# STM32F407_3.net
KiCad netlist of a schematic drawn in Altium Designer
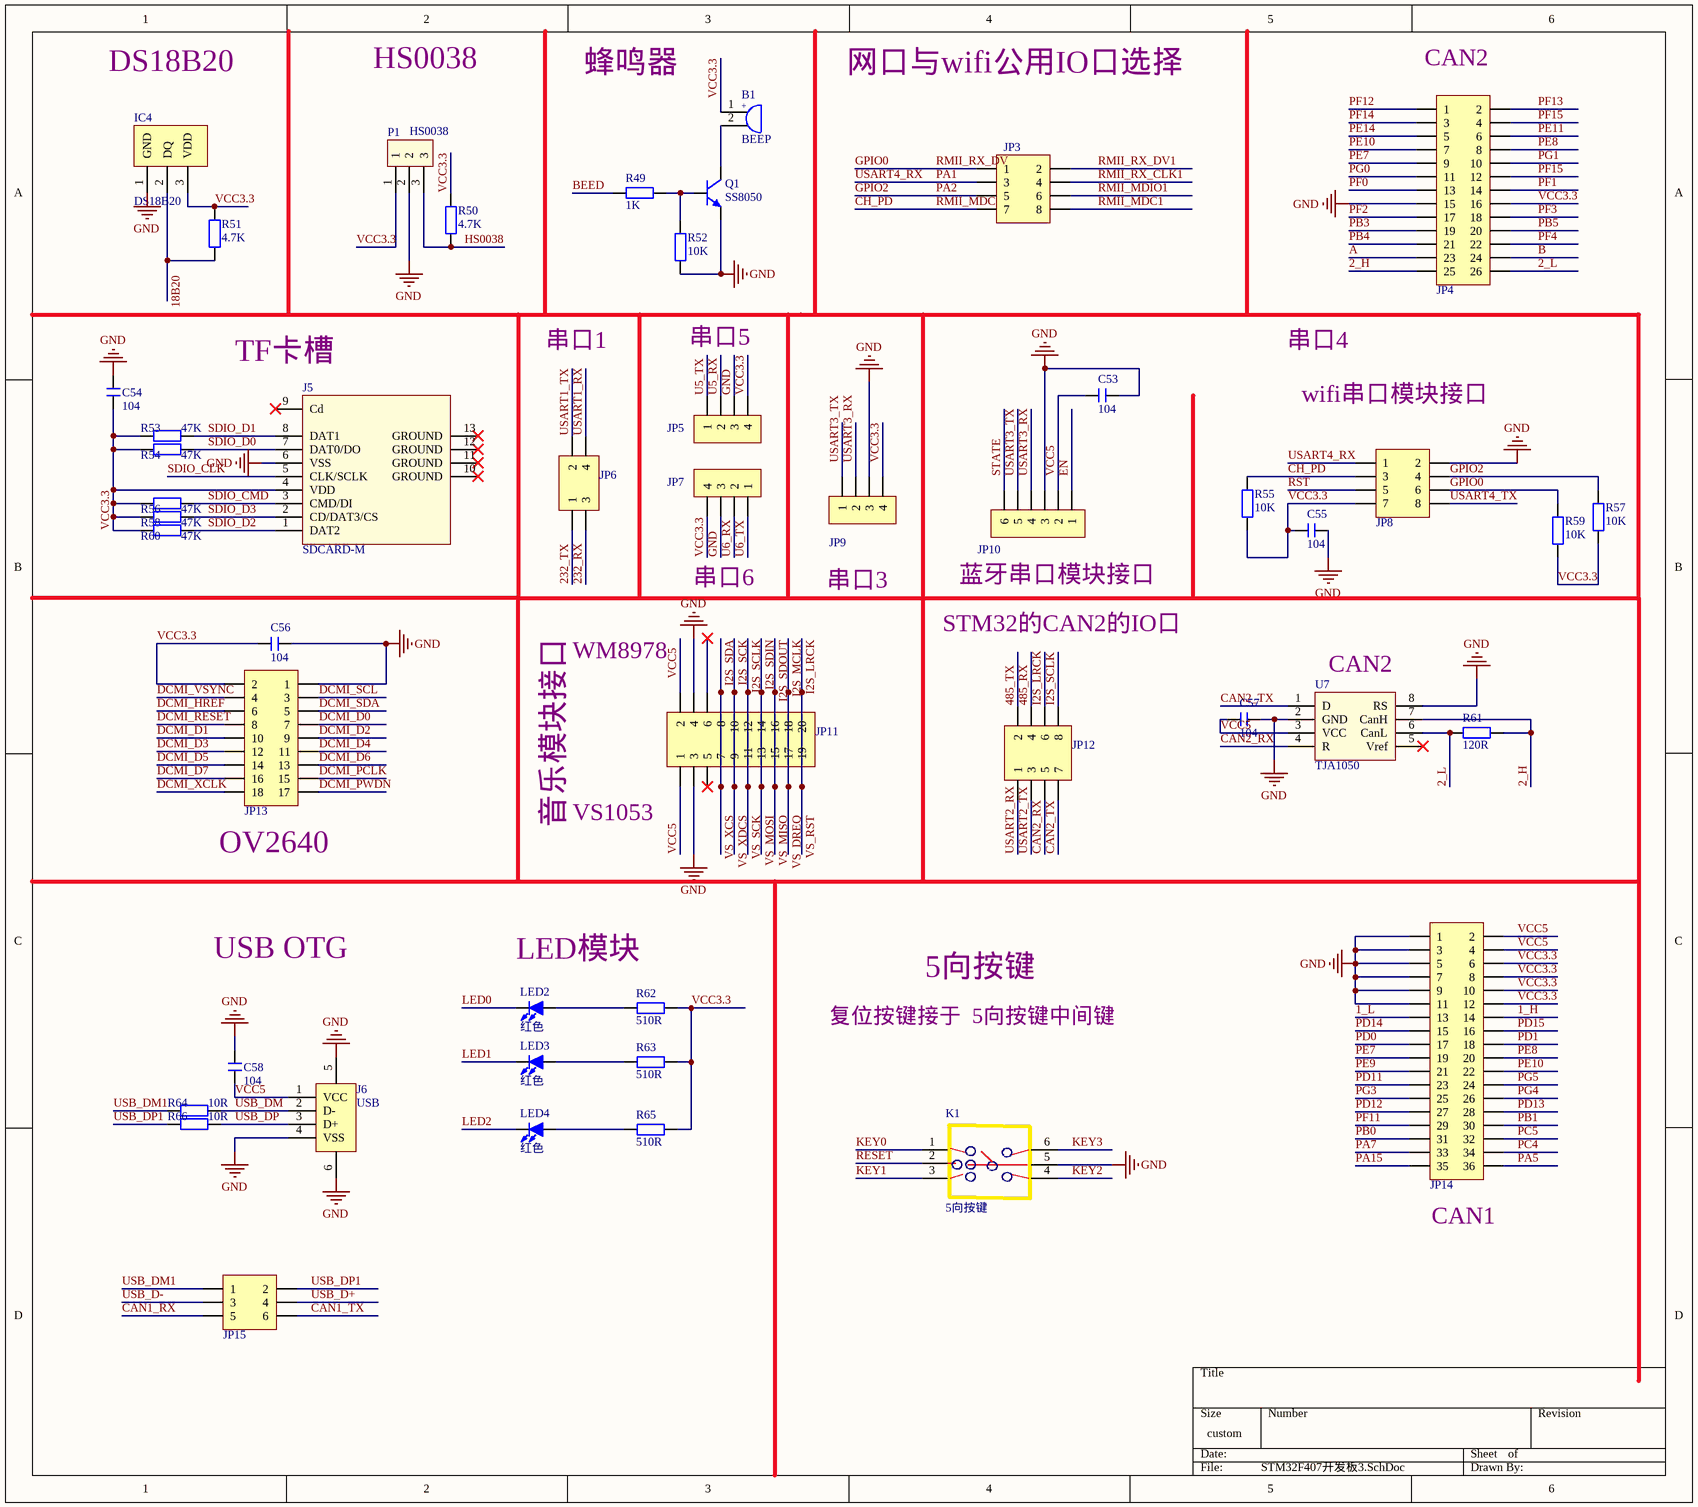
[diagram p0: STM32F407开发板3.SchDoc]

(export (version "E")
  (design (tool "Eeschema 10.0.6"))
  (components
    (comp (ref "B1")
      (value "BEEP")
      (footprint "BEEP 5x9x5.5")
      (description "蜂鸣器")
      (fields (field (name "版权归属") "源创客"))
      (libsource (lib "未分类器件") (part "BEEP"))
    )
    (comp (ref "C53")
      (value "104")
      (footprint "C 0603")
      (description "无极性贴片电容")
      (fields (field (name "版权归属") "源创客"))
      (libsource (lib "电阻-电容-电感") (part "C"))
    )
    (comp (ref "C54")
      (value "104")
      (footprint "C 0603")
      (description "无极性贴片电容")
      (fields (field (name "版权归属") "源创客"))
      (libsource (lib "电阻-电容-电感") (part "C"))
    )
    (comp (ref "C55")
      (value "104")
      (footprint "C 0603")
      (description "无极性贴片电容")
      (fields (field (name "版权归属") "源创客"))
      (libsource (lib "电阻-电容-电感") (part "C"))
    )
    (comp (ref "C56")
      (value "104")
      (footprint "C 0603")
      (description "无极性贴片电容")
      (fields (field (name "版权归属") "源创客"))
      (libsource (lib "电阻-电容-电感") (part "C"))
    )
    (comp (ref "C57")
      (value "104")
      (footprint "C 0603")
      (description "无极性贴片电容")
      (fields (field (name "版权归属") "源创客"))
      (libsource (lib "电阻-电容-电感") (part "C"))
    )
    (comp (ref "C58")
      (value "104")
      (footprint "C 0603")
      (description "无极性贴片电容")
      (fields (field (name "版权归属") "源创客"))
      (libsource (lib "电阻-电容-电感") (part "C"))
    )
    (comp (ref "IC4")
      (value "DS18B20")
      (footprint "TO92A")
      (description "数字温度计")
      (fields (field (name "版权归属") "源创客"))
      (libsource (lib "IC芯片") (part "DS18B20"))
    )
    (comp (ref "J5")
      (value "SDCARD-M")
      (footprint "Micro TF/SD")
      (description "TF卡槽")
      (libsource (lib "接口类") (part "SDCARD-M"))
    )
    (comp (ref "J6") (value "USB") (footprint "USB-A/S_A") (libsource (lib "接口类") (part "USB OTG")))
    (comp (ref "JP3")
      (value "Header 4X2")
      (footprint "HDR-4X2")
      (description "4*2P接插件")
      (fields (field (name "版权归属") "源创客"))
      (libsource (lib "") (part "Header 4X2_1"))
    )
    (comp (ref "JP4")
      (value "Header 2X11")
      (footprint "HDR-13X2")
      (description "13*2P接插件")
      (fields (field (name "版权归属") "源创客"))
      (libsource (lib "接插件") (part "Header 13X2"))
    )
    (comp (ref "JP5")
      (value "HDR-1X4")
      (footprint "HDR-1X4")
      (description "4P接插件")
      (fields (field (name "版权归属") "源创客"))
      (libsource (lib "接插件") (part "Header 4"))
    )
    (comp (ref "JP6")
      (value "Header2X2")
      (footprint "HDR-2X2")
      (description "2*2P接插件")
      (fields (field (name "版权归属") "源创客"))
      (libsource (lib "接插件") (part "Header 2X2"))
    )
    (comp (ref "JP7")
      (value "HDR-1X4")
      (footprint "HDR-1X4")
      (description "4P接插件")
      (fields (field (name "版权归属") "源创客"))
      (libsource (lib "") (part "Header 4_1"))
    )
    (comp (ref "JP8")
      (value "Header 4X2")
      (footprint "HDR-4X2")
      (description "4*2P接插件")
      (fields (field (name "版权归属") "源创客"))
      (libsource (lib "") (part "Header 4X2_1"))
    )
    (comp (ref "JP9")
      (value "HDR-1X4")
      (footprint "HDR-1X4")
      (description "4P接插件")
      (fields (field (name "版权归属") "源创客"))
      (libsource (lib "接插件") (part "Header 4"))
    )
    (comp (ref "JP10")
      (value "HDR-1X6")
      (footprint "HDR-1X6")
      (description "6P接插件")
      (fields (field (name "版权归属") "源创客"))
      (libsource (lib "接插件") (part "Header 6"))
    )
    (comp (ref "JP11")
      (value "Header 2X10")
      (footprint "HDR-10X2")
      (description "10*2P接插件")
      (fields (field (name "版权归属") "源创客"))
      (libsource (lib "接插件") (part "Header 10X2"))
    )
    (comp (ref "JP12")
      (value "Header 4X2")
      (footprint "HDR-4X2")
      (description "4*2P接插件")
      (fields (field (name "版权归属") "源创客"))
      (libsource (lib "接插件") (part "Header 4X2"))
    )
    (comp (ref "JP13")
      (value "Header 9X2")
      (footprint "HDR-9X2")
      (description "9*2P接插件")
      (fields (field (name "版权归属") "源创客"))
      (libsource (lib "接插件") (part "Header 9X2"))
    )
    (comp (ref "JP14")
      (value "Header 2X11")
      (footprint "HDR-18X2")
      (description "18*2P接插件")
      (fields (field (name "版权归属") "源创客"))
      (libsource (lib "接插件") (part "Header 18X2"))
    )
    (comp (ref "JP15")
      (value "Header3X2")
      (footprint "HDR-3X2")
      (description "3*2P接插件")
      (fields (field (name "版权归属") "源创客"))
      (libsource (lib "接插件") (part "Header 3X2"))
    )
    (comp (ref "K1") (value "5向按键") (footprint "五向按键") (libsource (lib "按键-开关") (part "5向按键")))
    (comp (ref "LED2")
      (value "红色")
      (footprint "LED 0603R")
      (description "5mm插件LED")
      (fields (field (name "版权归属") "源创客"))
      (libsource (lib "LED") (part "LED-5MM"))
    )
    (comp (ref "LED3")
      (value "红色")
      (footprint "LED 0603R")
      (description "5mm插件LED")
      (fields (field (name "版权归属") "源创客"))
      (libsource (lib "LED") (part "LED-5MM"))
    )
    (comp (ref "LED4")
      (value "红色")
      (footprint "LED 0603R")
      (description "5mm插件LED")
      (fields (field (name "版权归属") "源创客"))
      (libsource (lib "LED") (part "LED-5MM"))
    )
    (comp (ref "P1") (value "HS0038") (footprint "VS1838B-A") (libsource (lib "传感元件") (part "HS0038")))
    (comp (ref "Q1")
      (value "SS8050")
      (footprint "SOT23-3L")
      (description "高频放大-NPN型")
      (fields (field (name "版权归属") "源创客"))
      (libsource (lib "三极管") (part "8050-SMD"))
    )
    (comp (ref "R49")
      (value "1K")
      (footprint "R 0603")
      (description "贴片电阻")
      (fields (field (name "版权归属") "源创客"))
      (libsource (lib "电阻-电容-电感") (part "R"))
    )
    (comp (ref "R50")
      (value "4.7K")
      (footprint "R 0603")
      (description "贴片电阻")
      (fields (field (name "版权归属") "源创客"))
      (libsource (lib "电阻-电容-电感") (part "R"))
    )
    (comp (ref "R51")
      (value "4.7K")
      (footprint "R 0603")
      (description "贴片电阻")
      (fields (field (name "版权归属") "源创客"))
      (libsource (lib "电阻-电容-电感") (part "R"))
    )
    (comp (ref "R52")
      (value "10K")
      (footprint "R 0603")
      (description "贴片电阻")
      (fields (field (name "版权归属") "源创客"))
      (libsource (lib "电阻-电容-电感") (part "R"))
    )
    (comp (ref "R53")
      (value "47K")
      (footprint "R 0603")
      (description "贴片电阻")
      (fields (field (name "版权归属") "源创客"))
      (libsource (lib "电阻-电容-电感") (part "R"))
    )
    (comp (ref "R54")
      (value "47K")
      (footprint "R 0603")
      (description "贴片电阻")
      (fields (field (name "版权归属") "源创客"))
      (libsource (lib "电阻-电容-电感") (part "R"))
    )
    (comp (ref "R55")
      (value "10K")
      (footprint "R 0603")
      (description "贴片电阻")
      (fields (field (name "版权归属") "源创客"))
      (libsource (lib "电阻-电容-电感") (part "R"))
    )
    (comp (ref "R56")
      (value "47K")
      (footprint "R 0603")
      (description "贴片电阻")
      (fields (field (name "版权归属") "源创客"))
      (libsource (lib "电阻-电容-电感") (part "R"))
    )
    (comp (ref "R57")
      (value "10K")
      (footprint "R 0603")
      (description "贴片电阻")
      (fields (field (name "版权归属") "源创客"))
      (libsource (lib "电阻-电容-电感") (part "R"))
    )
    (comp (ref "R58")
      (value "47K")
      (footprint "R 0603")
      (description "贴片电阻")
      (fields (field (name "版权归属") "源创客"))
      (libsource (lib "电阻-电容-电感") (part "R"))
    )
    (comp (ref "R59")
      (value "10K")
      (footprint "R 0603")
      (description "贴片电阻")
      (fields (field (name "版权归属") "源创客"))
      (libsource (lib "电阻-电容-电感") (part "R"))
    )
    (comp (ref "R60")
      (value "47K")
      (footprint "R 0603")
      (description "贴片电阻")
      (fields (field (name "版权归属") "源创客"))
      (libsource (lib "电阻-电容-电感") (part "R"))
    )
    (comp (ref "R61")
      (value "120R")
      (footprint "R 0603")
      (description "贴片电阻")
      (fields (field (name "版权归属") "源创客"))
      (libsource (lib "电阻-电容-电感") (part "R"))
    )
    (comp (ref "R62")
      (value "510R")
      (footprint "R 0603")
      (description "贴片电阻")
      (fields (field (name "版权归属") "源创客"))
      (libsource (lib "电阻-电容-电感") (part "R"))
    )
    (comp (ref "R63")
      (value "510R")
      (footprint "R 0603")
      (description "贴片电阻")
      (fields (field (name "版权归属") "源创客"))
      (libsource (lib "电阻-电容-电感") (part "R"))
    )
    (comp (ref "R64")
      (value "10R")
      (footprint "R 0603")
      (description "贴片电阻")
      (fields (field (name "版权归属") "源创客"))
      (libsource (lib "电阻-电容-电感") (part "R"))
    )
    (comp (ref "R65")
      (value "510R")
      (footprint "R 0603")
      (description "贴片电阻")
      (fields (field (name "版权归属") "源创客"))
      (libsource (lib "电阻-电容-电感") (part "R"))
    )
    (comp (ref "R66")
      (value "10R")
      (footprint "R 0603")
      (description "贴片电阻")
      (fields (field (name "版权归属") "源创客"))
      (libsource (lib "电阻-电容-电感") (part "R"))
    )
    (comp (ref "U7") (value "TJA1050") (footprint "TJA1050") (libsource (lib "IC芯片") (part "TJA1050")))
  )
  (nets
    (net (code "1") (name "/1_H") (class "Default")
      (node (ref "JP14") (pin "14") (pinfunction "14_14") (pintype "passive"))
    )
    (net (code "2") (name "/1_L") (class "Default")
      (node (ref "JP14") (pin "13") (pinfunction "13_13") (pintype "passive"))
    )
    (net (code "3") (name "/2_H") (class "Default")
      (node (ref "JP4") (pin "25") (pinfunction "25_25") (pintype "passive"))
      (node (ref "R61") (pin "1") (pinfunction "1_1") (pintype "passive"))
      (node (ref "U7") (pin "7") (pinfunction "CanH_7") (pintype "passive"))
    )
    (net (code "4") (name "/2_L") (class "Default")
      (node (ref "JP4") (pin "26") (pinfunction "26_26") (pintype "passive"))
      (node (ref "R61") (pin "2") (pinfunction "2_2") (pintype "passive"))
      (node (ref "U7") (pin "6") (pinfunction "CanL_6") (pintype "passive"))
    )
    (net (code "5") (name "/18B20") (class "Default")
      (node (ref "IC4") (pin "2") (pinfunction "DQ_2") (pintype "passive"))
      (node (ref "R51") (pin "1") (pinfunction "1_1") (pintype "passive"))
    )
    (net (code "6") (name "/232_RX") (class "Default")
      (node (ref "JP6") (pin "3") (pinfunction "3_3") (pintype "passive"))
    )
    (net (code "7") (name "/232_TX") (class "Default")
      (node (ref "JP6") (pin "1") (pinfunction "1_1") (pintype "passive"))
    )
    (net (code "8") (name "/485_RX") (class "Default")
      (node (ref "JP12") (pin "4") (pinfunction "4_4") (pintype "passive"))
    )
    (net (code "9") (name "/485_TX") (class "Default")
      (node (ref "JP12") (pin "2") (pinfunction "2_2") (pintype "passive"))
    )
    (net (code "10") (name "/A") (class "Default")
      (node (ref "JP4") (pin "23") (pinfunction "23_23") (pintype "passive"))
    )
    (net (code "11") (name "/B") (class "Default")
      (node (ref "JP4") (pin "24") (pinfunction "24_24") (pintype "passive"))
    )
    (net (code "12") (name "/BEED") (class "Default")
      (node (ref "R49") (pin "2") (pinfunction "2_2") (pintype "passive"))
    )
    (net (code "13") (name "/CAN1_RX") (class "Default")
      (node (ref "JP15") (pin "5") (pinfunction "5_5") (pintype "passive"))
    )
    (net (code "14") (name "/CAN1_TX") (class "Default")
      (node (ref "JP15") (pin "6") (pinfunction "6_6") (pintype "passive"))
    )
    (net (code "15") (name "/CAN2_RX") (class "Default")
      (node (ref "JP12") (pin "5") (pinfunction "5_5") (pintype "passive"))
      (node (ref "U7") (pin "4") (pinfunction "R_4") (pintype "passive"))
    )
    (net (code "16") (name "/CAN2_TX") (class "Default")
      (node (ref "JP12") (pin "7") (pinfunction "7_7") (pintype "passive"))
      (node (ref "U7") (pin "1") (pinfunction "D_1") (pintype "passive"))
    )
    (net (code "17") (name "/CH_PD") (class "Default")
      (node (ref "JP3") (pin "7") (pinfunction "7_7") (pintype "passive"))
      (node (ref "JP8") (pin "3") (pinfunction "3_3") (pintype "passive"))
      (node (ref "R55") (pin "2") (pinfunction "2_2") (pintype "passive"))
    )
    (net (code "18") (name "/DCMI_D0") (class "Default")
      (node (ref "JP13") (pin "7") (pinfunction "7_7") (pintype "passive"))
    )
    (net (code "19") (name "/DCMI_D1") (class "Default")
      (node (ref "JP13") (pin "10") (pinfunction "10_10") (pintype "passive"))
    )
    (net (code "20") (name "/DCMI_D2") (class "Default")
      (node (ref "JP13") (pin "9") (pinfunction "9_9") (pintype "passive"))
    )
    (net (code "21") (name "/DCMI_D3") (class "Default")
      (node (ref "JP13") (pin "12") (pinfunction "12_12") (pintype "passive"))
    )
    (net (code "22") (name "/DCMI_D4") (class "Default")
      (node (ref "JP13") (pin "11") (pinfunction "11_11") (pintype "passive"))
    )
    (net (code "23") (name "/DCMI_D5") (class "Default")
      (node (ref "JP13") (pin "14") (pinfunction "14_14") (pintype "passive"))
    )
    (net (code "24") (name "/DCMI_D6") (class "Default")
      (node (ref "JP13") (pin "13") (pinfunction "13_13") (pintype "passive"))
    )
    (net (code "25") (name "/DCMI_D7") (class "Default")
      (node (ref "JP13") (pin "16") (pinfunction "16_16") (pintype "passive"))
    )
    (net (code "26") (name "/DCMI_HREF") (class "Default")
      (node (ref "JP13") (pin "6") (pinfunction "6_6") (pintype "passive"))
    )
    (net (code "27") (name "/DCMI_PCLK") (class "Default")
      (node (ref "JP13") (pin "15") (pinfunction "15_15") (pintype "passive"))
    )
    (net (code "28") (name "/DCMI_PWDN") (class "Default")
      (node (ref "JP13") (pin "17") (pinfunction "17_17") (pintype "passive"))
    )
    (net (code "29") (name "/DCMI_RESET") (class "Default")
      (node (ref "JP13") (pin "8") (pinfunction "8_8") (pintype "passive"))
    )
    (net (code "30") (name "/DCMI_SCL") (class "Default")
      (node (ref "JP13") (pin "3") (pinfunction "3_3") (pintype "passive"))
    )
    (net (code "31") (name "/DCMI_SDA") (class "Default")
      (node (ref "JP13") (pin "5") (pinfunction "5_5") (pintype "passive"))
    )
    (net (code "32") (name "/DCMI_VSYNC") (class "Default")
      (node (ref "JP13") (pin "4") (pinfunction "4_4") (pintype "passive"))
    )
    (net (code "33") (name "/DCMI_XCLK") (class "Default")
      (node (ref "JP13") (pin "18") (pinfunction "18_18") (pintype "passive"))
    )
    (net (code "34") (name "/EN") (class "Default")
      (node (ref "JP10") (pin "1") (pinfunction "1_1") (pintype "passive"))
    )
    (net (code "35") (name "/GPIO0") (class "Default")
      (node (ref "JP3") (pin "1") (pinfunction "1_1") (pintype "passive"))
      (node (ref "JP8") (pin "6") (pinfunction "6_6") (pintype "passive"))
      (node (ref "R59") (pin "2") (pinfunction "2_2") (pintype "passive"))
    )
    (net (code "36") (name "/GPIO2") (class "Default")
      (node (ref "JP3") (pin "5") (pinfunction "5_5") (pintype "passive"))
      (node (ref "JP8") (pin "4") (pinfunction "4_4") (pintype "passive"))
      (node (ref "R57") (pin "2") (pinfunction "2_2") (pintype "passive"))
    )
    (net (code "37") (name "/HS0038") (class "Default")
      (node (ref "P1") (pin "3") (pinfunction "3_3") (pintype "passive"))
      (node (ref "R50") (pin "1") (pinfunction "1_1") (pintype "passive"))
    )
    (net (code "38") (name "/I2S_LRCK") (class "Default")
      (node (ref "JP11") (pin "19") (pinfunction "19_19") (pintype "passive"))
      (node (ref "JP11") (pin "20") (pinfunction "20_20") (pintype "passive"))
      (node (ref "JP12") (pin "6") (pinfunction "6_6") (pintype "passive"))
    )
    (net (code "39") (name "/I2S_MCLK") (class "Default")
      (node (ref "JP11") (pin "17") (pinfunction "17_17") (pintype "passive"))
      (node (ref "JP11") (pin "18") (pinfunction "18_18") (pintype "passive"))
    )
    (net (code "40") (name "/I2S_SCK") (class "Default")
      (node (ref "JP11") (pin "10") (pinfunction "10_10") (pintype "passive"))
      (node (ref "JP11") (pin "9") (pinfunction "9_9") (pintype "passive"))
    )
    (net (code "41") (name "/I2S_SCLK") (class "Default")
      (node (ref "JP11") (pin "11") (pinfunction "11_11") (pintype "passive"))
      (node (ref "JP11") (pin "12") (pinfunction "12_12") (pintype "passive"))
      (node (ref "JP12") (pin "8") (pinfunction "8_8") (pintype "passive"))
    )
    (net (code "42") (name "/I2S_SDA") (class "Default")
      (node (ref "JP11") (pin "7") (pinfunction "7_7") (pintype "passive"))
      (node (ref "JP11") (pin "8") (pinfunction "8_8") (pintype "passive"))
    )
    (net (code "43") (name "/I2S_SDIN") (class "Default")
      (node (ref "JP11") (pin "13") (pinfunction "13_13") (pintype "passive"))
      (node (ref "JP11") (pin "14") (pinfunction "14_14") (pintype "passive"))
    )
    (net (code "44") (name "/I2S_SDOUT") (class "Default")
      (node (ref "JP11") (pin "15") (pinfunction "15_15") (pintype "passive"))
      (node (ref "JP11") (pin "16") (pinfunction "16_16") (pintype "passive"))
    )
    (net (code "45") (name "/KEY0") (class "Default")
      (node (ref "K1") (pin "1") (pinfunction "1_1") (pintype "passive"))
    )
    (net (code "46") (name "/KEY1") (class "Default")
      (node (ref "K1") (pin "3") (pinfunction "3_3") (pintype "passive"))
    )
    (net (code "47") (name "/KEY2") (class "Default")
      (node (ref "K1") (pin "4") (pinfunction "4_4") (pintype "passive"))
    )
    (net (code "48") (name "/KEY3") (class "Default")
      (node (ref "K1") (pin "6") (pinfunction "6_6") (pintype "passive"))
    )
    (net (code "49") (name "/LED0") (class "Default")
      (node (ref "LED2") (pin "2") (pinfunction "K_2") (pintype "passive"))
    )
    (net (code "50") (name "/LED1") (class "Default")
      (node (ref "LED3") (pin "2") (pinfunction "K_2") (pintype "passive"))
    )
    (net (code "51") (name "/LED2") (class "Default")
      (node (ref "LED4") (pin "2") (pinfunction "K_2") (pintype "passive"))
    )
    (net (code "52") (name "/PA1") (class "Default")
      (node (ref "JP3") (pin "3") (pinfunction "3_3") (pintype "passive"))
      (node (ref "JP8") (pin "1") (pinfunction "1_1") (pintype "passive"))
    )
    (net (code "53") (name "/PA5") (class "Default")
      (node (ref "JP14") (pin "36") (pinfunction "36_36") (pintype "passive"))
    )
    (net (code "54") (name "/PA7") (class "Default")
      (node (ref "JP14") (pin "33") (pinfunction "33_33") (pintype "passive"))
    )
    (net (code "55") (name "/PA15") (class "Default")
      (node (ref "JP14") (pin "35") (pinfunction "35_35") (pintype "passive"))
    )
    (net (code "56") (name "/PB0") (class "Default")
      (node (ref "JP14") (pin "31") (pinfunction "31_31") (pintype "passive"))
    )
    (net (code "57") (name "/PB1") (class "Default")
      (node (ref "JP14") (pin "30") (pinfunction "30_30") (pintype "passive"))
    )
    (net (code "58") (name "/PB3") (class "Default")
      (node (ref "JP4") (pin "19") (pinfunction "19_19") (pintype "passive"))
    )
    (net (code "59") (name "/PB4") (class "Default")
      (node (ref "JP4") (pin "21") (pinfunction "21_21") (pintype "passive"))
    )
    (net (code "60") (name "/PB5") (class "Default")
      (node (ref "JP4") (pin "20") (pinfunction "20_20") (pintype "passive"))
    )
    (net (code "61") (name "/PC4") (class "Default")
      (node (ref "JP14") (pin "34") (pinfunction "34_34") (pintype "passive"))
    )
    (net (code "62") (name "/PC5") (class "Default")
      (node (ref "JP14") (pin "32") (pinfunction "32_32") (pintype "passive"))
    )
    (net (code "63") (name "/PD0") (class "Default")
      (node (ref "JP14") (pin "17") (pinfunction "17_17") (pintype "passive"))
    )
    (net (code "64") (name "/PD1") (class "Default")
      (node (ref "JP14") (pin "18") (pinfunction "18_18") (pintype "passive"))
    )
    (net (code "65") (name "/PD11") (class "Default")
      (node (ref "JP14") (pin "23") (pinfunction "23_23") (pintype "passive"))
    )
    (net (code "66") (name "/PD12") (class "Default")
      (node (ref "JP14") (pin "27") (pinfunction "27_27") (pintype "passive"))
    )
    (net (code "67") (name "/PD13") (class "Default")
      (node (ref "JP14") (pin "28") (pinfunction "28_28") (pintype "passive"))
    )
    (net (code "68") (name "/PD14") (class "Default")
      (node (ref "JP14") (pin "15") (pinfunction "15_15") (pintype "passive"))
    )
    (net (code "69") (name "/PD15") (class "Default")
      (node (ref "JP14") (pin "16") (pinfunction "16_16") (pintype "passive"))
    )
    (net (code "70") (name "/PE7") (class "Default")
      (node (ref "JP14") (pin "19") (pinfunction "19_19") (pintype "passive"))
      (node (ref "JP4") (pin "9") (pinfunction "9_9") (pintype "passive"))
    )
    (net (code "71") (name "/PE8") (class "Default")
      (node (ref "JP14") (pin "20") (pinfunction "20_20") (pintype "passive"))
      (node (ref "JP4") (pin "8") (pinfunction "8_8") (pintype "passive"))
    )
    (net (code "72") (name "/PE9") (class "Default")
      (node (ref "JP14") (pin "21") (pinfunction "21_21") (pintype "passive"))
    )
    (net (code "73") (name "/PE10") (class "Default")
      (node (ref "JP14") (pin "22") (pinfunction "22_22") (pintype "passive"))
      (node (ref "JP4") (pin "7") (pinfunction "7_7") (pintype "passive"))
    )
    (net (code "74") (name "/PE11") (class "Default")
      (node (ref "JP4") (pin "6") (pinfunction "6_6") (pintype "passive"))
    )
    (net (code "75") (name "/PE14") (class "Default")
      (node (ref "JP4") (pin "5") (pinfunction "5_5") (pintype "passive"))
    )
    (net (code "76") (name "/PF0") (class "Default")
      (node (ref "JP4") (pin "13") (pinfunction "13_13") (pintype "passive"))
    )
    (net (code "77") (name "/PF1") (class "Default")
      (node (ref "JP4") (pin "14") (pinfunction "14_14") (pintype "passive"))
    )
    (net (code "78") (name "/PF2") (class "Default")
      (node (ref "JP4") (pin "17") (pinfunction "17_17") (pintype "passive"))
    )
    (net (code "79") (name "/PF3") (class "Default")
      (node (ref "JP4") (pin "18") (pinfunction "18_18") (pintype "passive"))
    )
    (net (code "80") (name "/PF4") (class "Default")
      (node (ref "JP4") (pin "22") (pinfunction "22_22") (pintype "passive"))
    )
    (net (code "81") (name "/PF11") (class "Default")
      (node (ref "JP14") (pin "29") (pinfunction "29_29") (pintype "passive"))
    )
    (net (code "82") (name "/PF12") (class "Default")
      (node (ref "JP4") (pin "1") (pinfunction "1_1") (pintype "passive"))
    )
    (net (code "83") (name "/PF13") (class "Default")
      (node (ref "JP4") (pin "2") (pinfunction "2_2") (pintype "passive"))
    )
    (net (code "84") (name "/PF14") (class "Default")
      (node (ref "JP4") (pin "3") (pinfunction "3_3") (pintype "passive"))
    )
    (net (code "85") (name "/PF15") (class "Default")
      (node (ref "JP4") (pin "12") (pinfunction "12_12") (pintype "passive"))
      (node (ref "JP4") (pin "4") (pinfunction "4_4") (pintype "passive"))
    )
    (net (code "86") (name "/PG0") (class "Default")
      (node (ref "JP4") (pin "11") (pinfunction "11_11") (pintype "passive"))
    )
    (net (code "87") (name "/PG1") (class "Default")
      (node (ref "JP4") (pin "10") (pinfunction "10_10") (pintype "passive"))
    )
    (net (code "88") (name "/PG3") (class "Default")
      (node (ref "JP14") (pin "25") (pinfunction "25_25") (pintype "passive"))
    )
    (net (code "89") (name "/PG4") (class "Default")
      (node (ref "JP14") (pin "26") (pinfunction "26_26") (pintype "passive"))
    )
    (net (code "90") (name "/PG5") (class "Default")
      (node (ref "JP14") (pin "24") (pinfunction "24_24") (pintype "passive"))
    )
    (net (code "91") (name "/RESET") (class "Default")
      (node (ref "K1") (pin "2") (pinfunction "2_2") (pintype "passive"))
    )
    (net (code "92") (name "/RMII_MDC1") (class "Default")
      (node (ref "JP3") (pin "8") (pinfunction "8_8") (pintype "passive"))
    )
    (net (code "93") (name "/RMII_MDIO1") (class "Default")
      (node (ref "JP3") (pin "6") (pinfunction "6_6") (pintype "passive"))
    )
    (net (code "94") (name "/RMII_RX_CLK1") (class "Default")
      (node (ref "JP3") (pin "4") (pinfunction "4_4") (pintype "passive"))
    )
    (net (code "95") (name "/RMII_RX_DV1") (class "Default")
      (node (ref "JP3") (pin "2") (pinfunction "2_2") (pintype "passive"))
    )
    (net (code "96") (name "/RST") (class "Default")
      (node (ref "JP8") (pin "5") (pinfunction "5_5") (pintype "passive"))
    )
    (net (code "97") (name "/SDIO_CLK") (class "Default")
      (node (ref "J5") (pin "5") (pinfunction "CLK/SCLK_5") (pintype "passive"))
    )
    (net (code "98") (name "/SDIO_CMD") (class "Default")
      (node (ref "J5") (pin "3") (pinfunction "CMD/DI_3") (pintype "passive"))
      (node (ref "R56") (pin "1") (pinfunction "1_1") (pintype "passive"))
    )
    (net (code "99") (name "/SDIO_D0") (class "Default")
      (node (ref "J5") (pin "7") (pinfunction "DAT0/DO_7") (pintype "passive"))
      (node (ref "R54") (pin "1") (pinfunction "1_1") (pintype "passive"))
    )
    (net (code "100") (name "/SDIO_D1") (class "Default")
      (node (ref "J5") (pin "8") (pinfunction "DAT1_8") (pintype "passive"))
      (node (ref "R53") (pin "1") (pinfunction "1_1") (pintype "passive"))
    )
    (net (code "101") (name "/SDIO_D2") (class "Default")
      (node (ref "J5") (pin "1") (pinfunction "DAT2_1") (pintype "passive"))
      (node (ref "R60") (pin "1") (pinfunction "1_1") (pintype "passive"))
    )
    (net (code "102") (name "/SDIO_D3") (class "Default")
      (node (ref "J5") (pin "2") (pinfunction "CD/DAT3/CS_2") (pintype "passive"))
      (node (ref "R58") (pin "1") (pinfunction "1_1") (pintype "passive"))
    )
    (net (code "103") (name "/STATE") (class "Default")
      (node (ref "JP10") (pin "6") (pinfunction "6_6") (pintype "passive"))
    )
    (net (code "104") (name "/U5_RX") (class "Default")
      (node (ref "JP5") (pin "2") (pinfunction "2_2") (pintype "passive"))
    )
    (net (code "105") (name "/U5_TX") (class "Default")
      (node (ref "JP5") (pin "1") (pinfunction "1_1") (pintype "passive"))
    )
    (net (code "106") (name "/U6_RX") (class "Default")
      (node (ref "JP7") (pin "2") (pinfunction "2_2") (pintype "passive"))
    )
    (net (code "107") (name "/U6_TX") (class "Default")
      (node (ref "JP7") (pin "1") (pinfunction "1_1") (pintype "passive"))
    )
    (net (code "108") (name "/USART1_RX") (class "Default")
      (node (ref "JP6") (pin "4") (pinfunction "4_4") (pintype "passive"))
    )
    (net (code "109") (name "/USART1_TX") (class "Default")
      (node (ref "JP6") (pin "2") (pinfunction "2_2") (pintype "passive"))
    )
    (net (code "110") (name "/USART2_RX") (class "Default")
      (node (ref "JP12") (pin "1") (pinfunction "1_1") (pintype "passive"))
    )
    (net (code "111") (name "/USART2_TX") (class "Default")
      (node (ref "JP12") (pin "3") (pinfunction "3_3") (pintype "passive"))
    )
    (net (code "112") (name "/USART3_RX") (class "Default")
      (node (ref "JP10") (pin "4") (pinfunction "4_4") (pintype "passive"))
      (node (ref "JP9") (pin "2") (pinfunction "2_2") (pintype "passive"))
    )
    (net (code "113") (name "/USART3_TX") (class "Default")
      (node (ref "JP10") (pin "5") (pinfunction "5_5") (pintype "passive"))
      (node (ref "JP9") (pin "1") (pinfunction "1_1") (pintype "passive"))
    )
    (net (code "114") (name "/USART4_TX") (class "Default")
      (node (ref "JP8") (pin "8") (pinfunction "8_8") (pintype "passive"))
    )
    (net (code "115") (name "/USB_D+") (class "Default")
      (node (ref "JP15") (pin "4") (pinfunction "4_4") (pintype "passive"))
    )
    (net (code "116") (name "/USB_D-") (class "Default")
      (node (ref "JP15") (pin "3") (pinfunction "3_3") (pintype "passive"))
    )
    (net (code "117") (name "/USB_DM") (class "Default")
      (node (ref "J6") (pin "2") (pinfunction "D-_2") (pintype "passive"))
      (node (ref "R64") (pin "1") (pinfunction "1_1") (pintype "passive"))
    )
    (net (code "118") (name "/USB_DM1") (class "Default")
      (node (ref "JP15") (pin "1") (pinfunction "1_1") (pintype "passive"))
      (node (ref "R64") (pin "2") (pinfunction "2_2") (pintype "passive"))
    )
    (net (code "119") (name "/USB_DP") (class "Default")
      (node (ref "J6") (pin "3") (pinfunction "D+_3") (pintype "passive"))
      (node (ref "R66") (pin "1") (pinfunction "1_1") (pintype "passive"))
    )
    (net (code "120") (name "/USB_DP1") (class "Default")
      (node (ref "JP15") (pin "2") (pinfunction "2_2") (pintype "passive"))
      (node (ref "R66") (pin "2") (pinfunction "2_2") (pintype "passive"))
    )
    (net (code "121") (name "/VCC3.3") (class "Default")
      (node (ref "B1") (pin "1") (pinfunction "1_1") (pintype "passive"))
      (node (ref "C54") (pin "1") (pinfunction "1_1") (pintype "passive"))
      (node (ref "C55") (pin "1") (pinfunction "1_1") (pintype "passive"))
      (node (ref "C56") (pin "2") (pinfunction "2_2") (pintype "passive"))
      (node (ref "IC4") (pin "3") (pinfunction "VDD_3") (pintype "passive"))
      (node (ref "J5") (pin "4") (pinfunction "VDD_4") (pintype "passive"))
      (node (ref "JP13") (pin "2") (pinfunction "2_2") (pintype "passive"))
      (node (ref "JP14") (pin "10") (pinfunction "10_10") (pintype "passive"))
      (node (ref "JP14") (pin "12") (pinfunction "12_12") (pintype "passive"))
      (node (ref "JP14") (pin "6") (pinfunction "6_6") (pintype "passive"))
      (node (ref "JP14") (pin "8") (pinfunction "8_8") (pintype "passive"))
      (node (ref "JP4") (pin "16") (pinfunction "16_16") (pintype "passive"))
      (node (ref "JP5") (pin "4") (pinfunction "4_4") (pintype "passive"))
      (node (ref "JP7") (pin "4") (pinfunction "4_4") (pintype "passive"))
      (node (ref "JP8") (pin "7") (pinfunction "7_7") (pintype "passive"))
      (node (ref "JP9") (pin "4") (pinfunction "4_4") (pintype "passive"))
      (node (ref "P1") (pin "1") (pinfunction "1_1") (pintype "passive"))
      (node (ref "R50") (pin "2") (pinfunction "2_2") (pintype "passive"))
      (node (ref "R51") (pin "2") (pinfunction "2_2") (pintype "passive"))
      (node (ref "R53") (pin "2") (pinfunction "2_2") (pintype "passive"))
      (node (ref "R54") (pin "2") (pinfunction "2_2") (pintype "passive"))
      (node (ref "R55") (pin "1") (pinfunction "1_1") (pintype "passive"))
      (node (ref "R56") (pin "2") (pinfunction "2_2") (pintype "passive"))
      (node (ref "R57") (pin "1") (pinfunction "1_1") (pintype "passive"))
      (node (ref "R58") (pin "2") (pinfunction "2_2") (pintype "passive"))
      (node (ref "R59") (pin "1") (pinfunction "1_1") (pintype "passive"))
      (node (ref "R60") (pin "2") (pinfunction "2_2") (pintype "passive"))
      (node (ref "R62") (pin "1") (pinfunction "1_1") (pintype "passive"))
      (node (ref "R63") (pin "1") (pinfunction "1_1") (pintype "passive"))
      (node (ref "R65") (pin "1") (pinfunction "1_1") (pintype "passive"))
    )
    (net (code "122") (name "/VCC5") (class "Default")
      (node (ref "C53") (pin "2") (pinfunction "2_2") (pintype "passive"))
      (node (ref "C57") (pin "1") (pinfunction "1_1") (pintype "passive"))
      (node (ref "C58") (pin "1") (pinfunction "1_1") (pintype "passive"))
      (node (ref "J6") (pin "1") (pinfunction "VCC_1") (pintype "passive"))
      (node (ref "JP10") (pin "2") (pinfunction "2_2") (pintype "passive"))
      (node (ref "JP11") (pin "1") (pinfunction "1_1") (pintype "passive"))
      (node (ref "JP11") (pin "2") (pinfunction "2_2") (pintype "passive"))
      (node (ref "JP14") (pin "2") (pinfunction "2_2") (pintype "passive"))
      (node (ref "JP14") (pin "4") (pinfunction "4_4") (pintype "passive"))
      (node (ref "U7") (pin "3") (pinfunction "VCC_3") (pintype "passive"))
    )
    (net (code "123") (name "GND") (class "Default")
      (node (ref "C53") (pin "1") (pinfunction "1_1") (pintype "passive"))
      (node (ref "C54") (pin "2") (pinfunction "2_2") (pintype "passive"))
      (node (ref "C55") (pin "2") (pinfunction "2_2") (pintype "passive"))
      (node (ref "C56") (pin "1") (pinfunction "1_1") (pintype "passive"))
      (node (ref "C57") (pin "2") (pinfunction "2_2") (pintype "passive"))
      (node (ref "C58") (pin "2") (pinfunction "2_2") (pintype "passive"))
      (node (ref "IC4") (pin "1") (pinfunction "GND_1") (pintype "passive"))
      (node (ref "J5") (pin "6") (pinfunction "VSS_6") (pintype "passive"))
      (node (ref "J6") (pin "4") (pinfunction "VSS_4") (pintype "passive"))
      (node (ref "J6") (pin "5") (pinfunction "5_5") (pintype "passive"))
      (node (ref "J6") (pin "6") (pinfunction "6_6") (pintype "passive"))
      (node (ref "JP10") (pin "3") (pinfunction "3_3") (pintype "passive"))
      (node (ref "JP11") (pin "3") (pinfunction "3_3") (pintype "passive"))
      (node (ref "JP11") (pin "4") (pinfunction "4_4") (pintype "passive"))
      (node (ref "JP13") (pin "1") (pinfunction "1_1") (pintype "passive"))
      (node (ref "JP14") (pin "1") (pinfunction "1_1") (pintype "passive"))
      (node (ref "JP14") (pin "11") (pinfunction "11_11") (pintype "passive"))
      (node (ref "JP14") (pin "3") (pinfunction "3_3") (pintype "passive"))
      (node (ref "JP14") (pin "5") (pinfunction "5_5") (pintype "passive"))
      (node (ref "JP14") (pin "7") (pinfunction "7_7") (pintype "passive"))
      (node (ref "JP14") (pin "9") (pinfunction "9_9") (pintype "passive"))
      (node (ref "JP4") (pin "15") (pinfunction "15_15") (pintype "passive"))
      (node (ref "JP5") (pin "3") (pinfunction "3_3") (pintype "passive"))
      (node (ref "JP7") (pin "3") (pinfunction "3_3") (pintype "passive"))
      (node (ref "JP8") (pin "2") (pinfunction "2_2") (pintype "passive"))
      (node (ref "JP9") (pin "3") (pinfunction "3_3") (pintype "passive"))
      (node (ref "K1") (pin "5") (pinfunction "5_5") (pintype "passive"))
      (node (ref "P1") (pin "2") (pinfunction "2_2") (pintype "passive"))
      (node (ref "Q1") (pin "2") (pinfunction "E_2") (pintype "passive"))
      (node (ref "R52") (pin "1") (pinfunction "1_1") (pintype "passive"))
      (node (ref "U7") (pin "2") (pinfunction "GND_2") (pintype "passive"))
      (node (ref "U7") (pin "8") (pinfunction "RS_8") (pintype "passive"))
    )
    (net (code "124") (name "Net-(LED2-A)") (class "Default")
      (node (ref "LED2") (pin "1") (pinfunction "A_1") (pintype "passive"))
      (node (ref "R62") (pin "2") (pinfunction "2_2") (pintype "passive"))
    )
    (net (code "125") (name "Net-(LED3-A)") (class "Default")
      (node (ref "LED3") (pin "1") (pinfunction "A_1") (pintype "passive"))
      (node (ref "R63") (pin "2") (pinfunction "2_2") (pintype "passive"))
    )
    (net (code "126") (name "Net-(LED4-A)") (class "Default")
      (node (ref "LED4") (pin "1") (pinfunction "A_1") (pintype "passive"))
      (node (ref "R65") (pin "2") (pinfunction "2_2") (pintype "passive"))
    )
    (net (code "127") (name "Net-(Q1-B)") (class "Default")
      (node (ref "Q1") (pin "1") (pinfunction "B_1") (pintype "passive"))
      (node (ref "R49") (pin "1") (pinfunction "1_1") (pintype "passive"))
      (node (ref "R52") (pin "2") (pinfunction "2_2") (pintype "passive"))
    )
    (net (code "128") (name "Net-(Q1-C)") (class "Default")
      (node (ref "B1") (pin "2") (pinfunction "2_2") (pintype "passive"))
      (node (ref "Q1") (pin "3") (pinfunction "C_3") (pintype "passive"))
    )
    (net (code "129") (name "unconnected-(J5-Cd-Pad9)") (class "Default")
      (node (ref "J5") (pin "9") (pinfunction "Cd_9") (pintype "passive+no_connect"))
    )
    (net (code "130") (name "unconnected-(J5-GROUND-Pad10)") (class "Default")
      (node (ref "J5") (pin "10") (pinfunction "GROUND_10") (pintype "passive+no_connect"))
    )
    (net (code "131") (name "unconnected-(J5-GROUND-Pad11)") (class "Default")
      (node (ref "J5") (pin "11") (pinfunction "GROUND_11") (pintype "passive+no_connect"))
    )
    (net (code "132") (name "unconnected-(J5-GROUND-Pad12)") (class "Default")
      (node (ref "J5") (pin "12") (pinfunction "GROUND_12") (pintype "passive+no_connect"))
    )
    (net (code "133") (name "unconnected-(J5-GROUND-Pad13)") (class "Default")
      (node (ref "J5") (pin "13") (pinfunction "GROUND_13") (pintype "passive+no_connect"))
    )
    (net (code "134") (name "unconnected-(JP11-Pad5)") (class "Default")
      (node (ref "JP11") (pin "5") (pinfunction "5_5") (pintype "passive+no_connect"))
    )
    (net (code "135") (name "unconnected-(JP11-Pad6)") (class "Default")
      (node (ref "JP11") (pin "6") (pinfunction "6_6") (pintype "passive+no_connect"))
    )
    (net (code "136") (name "unconnected-(U7-Vref-Pad5)") (class "Default")
      (node (ref "U7") (pin "5") (pinfunction "Vref_5") (pintype "passive+no_connect"))
    )
  )
)
